# NFC_reva.net
KiCad netlist of a schematic drawn in EAGLE
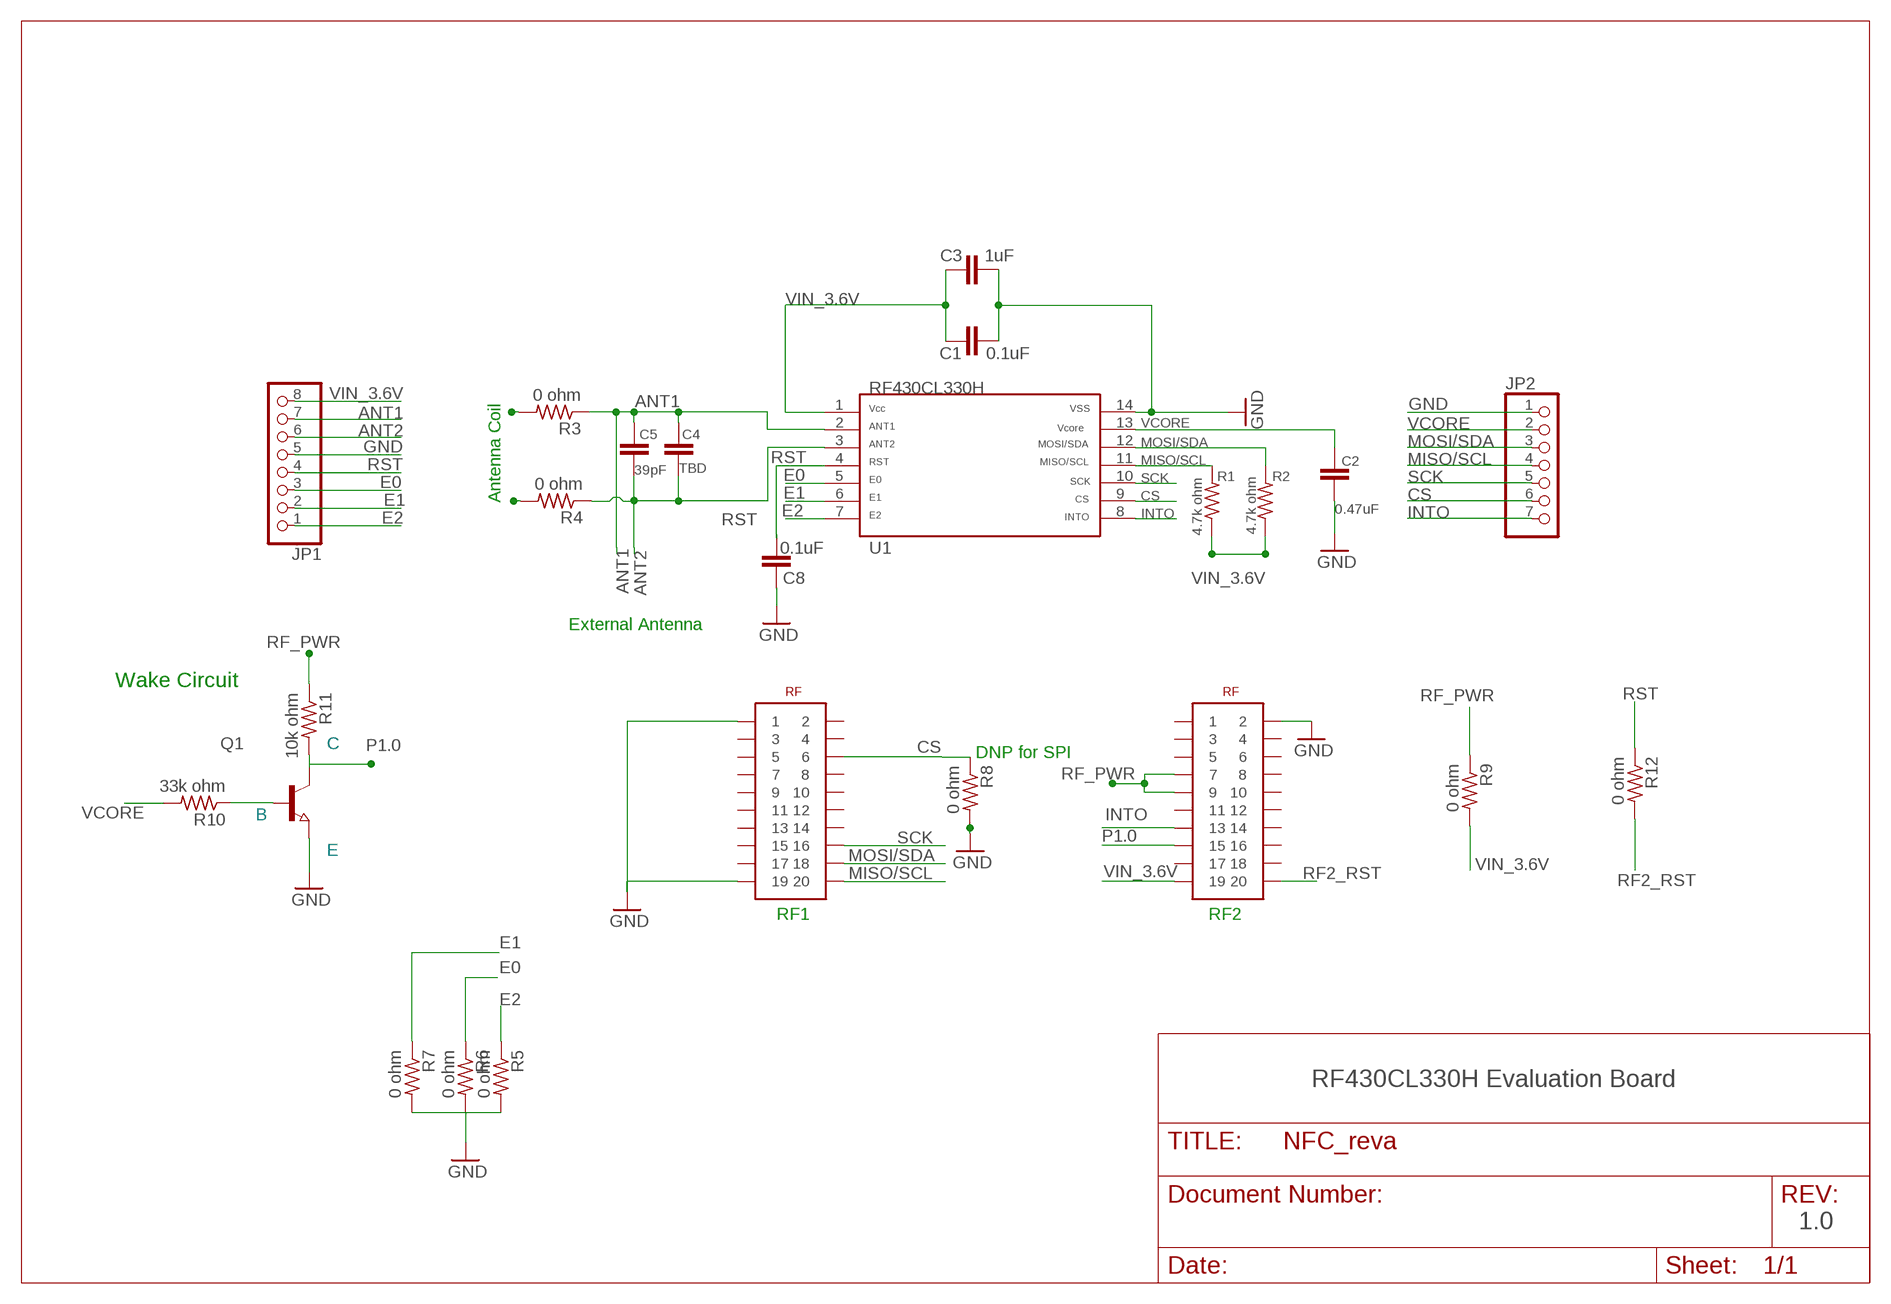
[diagram p0: schematic, sheet 1]

(export (version "E")
  (design (tool "Eeschema 10.0.6"))
  (components
    (comp (ref "C1")
      (value "0.1uF")
      (footprint "eagle-import:C0603")
      (libsource (lib "eagle-import") (part "C-EUC0603"))
    )
    (comp (ref "C2")
      (value "0.47uF")
      (footprint "eagle-import:C0603")
      (libsource (lib "eagle-import") (part "C-EUC0603"))
    )
    (comp (ref "C3")
      (value "1uF")
      (footprint "eagle-import:C0603")
      (libsource (lib "eagle-import") (part "C-EUC0603"))
    )
    (comp (ref "C4")
      (value "TBD")
      (footprint "eagle-import:C0603")
      (libsource (lib "eagle-import") (part "C-EUC0603"))
    )
    (comp (ref "C5")
      (value "39pF")
      (footprint "eagle-import:C0603")
      (libsource (lib "eagle-import") (part "C-EUC0603"))
    )
    (comp (ref "C8")
      (value "0.1uF")
      (footprint "eagle-import:C0603")
      (libsource (lib "eagle-import") (part "C-EUC0603"))
    )
    (comp (ref "JP1")
      (value "PINHD-1X8")
      (footprint "eagle-import:1X08")
      (libsource (lib "eagle-import") (part "PINHD-1X8"))
    )
    (comp (ref "JP2")
      (value "PINHD-1X7")
      (footprint "eagle-import:1X07")
      (libsource (lib "eagle-import") (part "PINHD-1X7"))
    )
    (comp (ref "Q1")
      (value "NPN-TRANSISTOR_SOT23")
      (footprint "eagle-import:SOT23")
      (libsource (lib "eagle-import") (part "NPN-TRANSISTOR_SOT23"))
    )
    (comp (ref "R1")
      (value "4.7k ohm")
      (footprint "eagle-import:R0402")
      (libsource (lib "eagle-import") (part "R-US_R0402"))
    )
    (comp (ref "R2")
      (value "4.7k ohm")
      (footprint "eagle-import:R0402")
      (libsource (lib "eagle-import") (part "R-US_R0402"))
    )
    (comp (ref "R3")
      (value "0 ohm")
      (footprint "eagle-import:R0402")
      (libsource (lib "eagle-import") (part "R-US_R0402"))
    )
    (comp (ref "R4")
      (value "0 ohm")
      (footprint "eagle-import:R0402")
      (libsource (lib "eagle-import") (part "R-US_R0402"))
    )
    (comp (ref "R5")
      (value "0 ohm")
      (footprint "eagle-import:R0402")
      (libsource (lib "eagle-import") (part "R-US_R0402"))
    )
    (comp (ref "R6")
      (value "0 ohm")
      (footprint "eagle-import:R0402")
      (libsource (lib "eagle-import") (part "R-US_R0402"))
    )
    (comp (ref "R7")
      (value "0 ohm")
      (footprint "eagle-import:R0402")
      (libsource (lib "eagle-import") (part "R-US_R0402"))
    )
    (comp (ref "R8")
      (value "0 ohm")
      (footprint "eagle-import:R0402")
      (libsource (lib "eagle-import") (part "R-US_R0402"))
    )
    (comp (ref "R9")
      (value "0 ohm")
      (footprint "eagle-import:R0402")
      (libsource (lib "eagle-import") (part "R-US_R0402"))
    )
    (comp (ref "R10")
      (value "33k ohm")
      (footprint "eagle-import:R0402")
      (libsource (lib "eagle-import") (part "R-US_R0402"))
    )
    (comp (ref "R11")
      (value "10k ohm")
      (footprint "eagle-import:R0402")
      (libsource (lib "eagle-import") (part "R-US_R0402"))
    )
    (comp (ref "R12")
      (value "0 ohm")
      (footprint "eagle-import:R0402")
      (libsource (lib "eagle-import") (part "R-US_R0402"))
    )
    (comp (ref "RF_HEADER")
      (value "EM_HEADER")
      (footprint "eagle-import:TFM-110-02-SM-D-A-K")
      (libsource (lib "eagle-import") (part "EM_HEADER"))
    )
    (comp (ref "U1")
      (value "RF430CL330H")
      (footprint "eagle-import:PW14")
      (libsource (lib "eagle-import") (part "RF430CL330H"))
    )
  )
  (nets
    (net (code "1") (name "/ANT1") (class "Default")
      (node (ref "C4") (pin "1") (pinfunction "1_1") (pintype "passive"))
      (node (ref "C5") (pin "1") (pinfunction "1_1") (pintype "passive"))
      (node (ref "JP1") (pin "7") (pinfunction "7_7") (pintype "passive"))
      (node (ref "R3") (pin "1") (pinfunction "1_1") (pintype "passive"))
      (node (ref "U1") (pin "2") (pinfunction "2_2") (pintype "bidirectional"))
    )
    (net (code "2") (name "/ANT2") (class "Default")
      (node (ref "C4") (pin "2") (pinfunction "2_2") (pintype "passive"))
      (node (ref "C5") (pin "2") (pinfunction "2_2") (pintype "passive"))
      (node (ref "JP1") (pin "6") (pinfunction "6_6") (pintype "passive"))
      (node (ref "R4") (pin "1") (pinfunction "1_1") (pintype "passive"))
      (node (ref "U1") (pin "3") (pinfunction "3_3") (pintype "bidirectional"))
    )
    (net (code "3") (name "/CS") (class "Default")
      (node (ref "JP2") (pin "6") (pinfunction "6_6") (pintype "passive"))
      (node (ref "R8") (pin "1") (pinfunction "1_1") (pintype "passive"))
      (node (ref "RF_HEADER") (pin "6") (pinfunction "6_6") (pintype "bidirectional"))
      (node (ref "U1") (pin "9") (pinfunction "9_9") (pintype "bidirectional"))
    )
    (net (code "4") (name "/E0") (class "Default")
      (node (ref "JP1") (pin "3") (pinfunction "3_3") (pintype "passive"))
      (node (ref "R6") (pin "1") (pinfunction "1_1") (pintype "passive"))
      (node (ref "U1") (pin "5") (pinfunction "5_5") (pintype "bidirectional"))
    )
    (net (code "5") (name "/E1") (class "Default")
      (node (ref "JP1") (pin "2") (pinfunction "2_2") (pintype "passive"))
      (node (ref "R7") (pin "1") (pinfunction "1_1") (pintype "passive"))
      (node (ref "U1") (pin "6") (pinfunction "6_6") (pintype "bidirectional"))
    )
    (net (code "6") (name "/E2") (class "Default")
      (node (ref "JP1") (pin "1") (pinfunction "1_1") (pintype "passive"))
      (node (ref "R5") (pin "1") (pinfunction "1_1") (pintype "passive"))
      (node (ref "U1") (pin "7") (pinfunction "7_7") (pintype "bidirectional"))
    )
    (net (code "7") (name "/INTO") (class "Default")
      (node (ref "JP2") (pin "7") (pinfunction "7_7") (pintype "passive"))
      (node (ref "RF_HEADER") (pin "33") (pinfunction "13_33") (pintype "bidirectional"))
      (node (ref "U1") (pin "8") (pinfunction "8_8") (pintype "bidirectional"))
    )
    (net (code "8") (name "/MISO{slash}SCL") (class "Default")
      (node (ref "JP2") (pin "4") (pinfunction "4_4") (pintype "passive"))
      (node (ref "R1") (pin "2") (pinfunction "2_2") (pintype "passive"))
      (node (ref "RF_HEADER") (pin "20") (pinfunction "20_20") (pintype "bidirectional"))
      (node (ref "U1") (pin "11") (pinfunction "11_11") (pintype "bidirectional"))
    )
    (net (code "9") (name "/MOSI{slash}SDA") (class "Default")
      (node (ref "JP2") (pin "3") (pinfunction "3_3") (pintype "passive"))
      (node (ref "R2") (pin "2") (pinfunction "2_2") (pintype "passive"))
      (node (ref "RF_HEADER") (pin "18") (pinfunction "18_18") (pintype "bidirectional"))
      (node (ref "U1") (pin "12") (pinfunction "12_12") (pintype "bidirectional"))
    )
    (net (code "10") (name "/P1.0") (class "Default")
      (node (ref "Q1") (pin "3") (pinfunction "C_3") (pintype "passive"))
      (node (ref "R11") (pin "2") (pinfunction "2_2") (pintype "passive"))
      (node (ref "RF_HEADER") (pin "35") (pinfunction "15_35") (pintype "bidirectional"))
    )
    (net (code "11") (name "/RF2_RST") (class "Default")
      (node (ref "R12") (pin "2") (pinfunction "2_2") (pintype "passive"))
      (node (ref "RF_HEADER") (pin "40") (pinfunction "20_40") (pintype "bidirectional"))
    )
    (net (code "12") (name "/RF_PWR") (class "Default")
      (node (ref "R11") (pin "1") (pinfunction "1_1") (pintype "passive"))
      (node (ref "R9") (pin "1") (pinfunction "1_1") (pintype "passive"))
      (node (ref "RF_HEADER") (pin "27") (pinfunction "7_27") (pintype "bidirectional"))
      (node (ref "RF_HEADER") (pin "29") (pinfunction "9_29") (pintype "bidirectional"))
    )
    (net (code "13") (name "/RST") (class "Default")
      (node (ref "C8") (pin "2") (pinfunction "2_2") (pintype "passive"))
      (node (ref "JP1") (pin "4") (pinfunction "4_4") (pintype "passive"))
      (node (ref "R12") (pin "1") (pinfunction "1_1") (pintype "passive"))
      (node (ref "U1") (pin "4") (pinfunction "4_4") (pintype "bidirectional"))
    )
    (net (code "14") (name "/SCK") (class "Default")
      (node (ref "JP2") (pin "5") (pinfunction "5_5") (pintype "passive"))
      (node (ref "RF_HEADER") (pin "16") (pinfunction "16_16") (pintype "bidirectional"))
      (node (ref "U1") (pin "10") (pinfunction "10_10") (pintype "bidirectional"))
    )
    (net (code "15") (name "/VCORE") (class "Default")
      (node (ref "C2") (pin "1") (pinfunction "1_1") (pintype "passive"))
      (node (ref "JP2") (pin "2") (pinfunction "2_2") (pintype "passive"))
      (node (ref "R10") (pin "2") (pinfunction "2_2") (pintype "passive"))
      (node (ref "U1") (pin "13") (pinfunction "13_13") (pintype "bidirectional"))
    )
    (net (code "16") (name "/VIN_3.6V") (class "Default")
      (node (ref "C1") (pin "1") (pinfunction "1_1") (pintype "passive"))
      (node (ref "C3") (pin "1") (pinfunction "1_1") (pintype "passive"))
      (node (ref "JP1") (pin "8") (pinfunction "8_8") (pintype "passive"))
      (node (ref "R1") (pin "1") (pinfunction "1_1") (pintype "passive"))
      (node (ref "R2") (pin "1") (pinfunction "1_1") (pintype "passive"))
      (node (ref "R9") (pin "2") (pinfunction "2_2") (pintype "passive"))
      (node (ref "RF_HEADER") (pin "39") (pinfunction "19_39") (pintype "bidirectional"))
      (node (ref "U1") (pin "1") (pinfunction "1_1") (pintype "bidirectional"))
    )
    (net (code "17") (name "GND") (class "Default")
      (node (ref "C1") (pin "2") (pinfunction "2_2") (pintype "passive"))
      (node (ref "C2") (pin "2") (pinfunction "2_2") (pintype "passive"))
      (node (ref "C3") (pin "2") (pinfunction "2_2") (pintype "passive"))
      (node (ref "C8") (pin "1") (pinfunction "1_1") (pintype "passive"))
      (node (ref "JP1") (pin "5") (pinfunction "5_5") (pintype "passive"))
      (node (ref "JP2") (pin "1") (pinfunction "1_1") (pintype "passive"))
      (node (ref "Q1") (pin "2") (pinfunction "E_2") (pintype "passive"))
      (node (ref "R5") (pin "2") (pinfunction "2_2") (pintype "passive"))
      (node (ref "R6") (pin "2") (pinfunction "2_2") (pintype "passive"))
      (node (ref "R7") (pin "2") (pinfunction "2_2") (pintype "passive"))
      (node (ref "R8") (pin "2") (pinfunction "2_2") (pintype "passive"))
      (node (ref "RF_HEADER") (pin "1") (pinfunction "1_1") (pintype "bidirectional"))
      (node (ref "RF_HEADER") (pin "19") (pinfunction "19_19") (pintype "bidirectional"))
      (node (ref "RF_HEADER") (pin "22") (pinfunction "2_22") (pintype "bidirectional"))
      (node (ref "U1") (pin "14") (pinfunction "14_14") (pintype "bidirectional"))
    )
    (net (code "18") (name "Net-(Q1-B)") (class "Default")
      (node (ref "Q1") (pin "1") (pinfunction "B_1") (pintype "passive"))
      (node (ref "R10") (pin "1") (pinfunction "1_1") (pintype "passive"))
    )
    (net (code "19") (name "unconnected-(R3-Pad2)") (class "Default")
      (node (ref "R3") (pin "2") (pinfunction "2_2") (pintype "passive"))
    )
    (net (code "20") (name "unconnected-(R4-Pad2)") (class "Default")
      (node (ref "R4") (pin "2") (pinfunction "2_2") (pintype "passive"))
    )
    (net (code "21") (name "unconnected-(RF_HEADER-Pad2)") (class "Default")
      (node (ref "RF_HEADER") (pin "2") (pinfunction "2_2") (pintype "bidirectional"))
    )
    (net (code "22") (name "unconnected-(RF_HEADER-Pad3)") (class "Default")
      (node (ref "RF_HEADER") (pin "3") (pinfunction "3_3") (pintype "bidirectional"))
    )
    (net (code "23") (name "unconnected-(RF_HEADER-Pad4)") (class "Default")
      (node (ref "RF_HEADER") (pin "4") (pinfunction "4_4") (pintype "bidirectional"))
    )
    (net (code "24") (name "unconnected-(RF_HEADER-Pad5)") (class "Default")
      (node (ref "RF_HEADER") (pin "5") (pinfunction "5_5") (pintype "bidirectional"))
    )
    (net (code "25") (name "unconnected-(RF_HEADER-Pad7)") (class "Default")
      (node (ref "RF_HEADER") (pin "7") (pinfunction "7_7") (pintype "bidirectional"))
    )
    (net (code "26") (name "unconnected-(RF_HEADER-Pad8)") (class "Default")
      (node (ref "RF_HEADER") (pin "8") (pinfunction "8_8") (pintype "bidirectional"))
    )
    (net (code "27") (name "unconnected-(RF_HEADER-Pad9)") (class "Default")
      (node (ref "RF_HEADER") (pin "9") (pinfunction "9_9") (pintype "bidirectional"))
    )
    (net (code "28") (name "unconnected-(RF_HEADER-Pad10)") (class "Default")
      (node (ref "RF_HEADER") (pin "10") (pinfunction "10_10") (pintype "bidirectional"))
    )
    (net (code "29") (name "unconnected-(RF_HEADER-Pad11)") (class "Default")
      (node (ref "RF_HEADER") (pin "11") (pinfunction "11_11") (pintype "bidirectional"))
    )
    (net (code "30") (name "unconnected-(RF_HEADER-Pad12)") (class "Default")
      (node (ref "RF_HEADER") (pin "12") (pinfunction "12_12") (pintype "bidirectional"))
    )
    (net (code "31") (name "unconnected-(RF_HEADER-Pad13)") (class "Default")
      (node (ref "RF_HEADER") (pin "13") (pinfunction "13_13") (pintype "bidirectional"))
    )
    (net (code "32") (name "unconnected-(RF_HEADER-Pad14)") (class "Default")
      (node (ref "RF_HEADER") (pin "14") (pinfunction "14_14") (pintype "bidirectional"))
    )
    (net (code "33") (name "unconnected-(RF_HEADER-Pad15)") (class "Default")
      (node (ref "RF_HEADER") (pin "15") (pinfunction "15_15") (pintype "bidirectional"))
    )
    (net (code "34") (name "unconnected-(RF_HEADER-Pad17)") (class "Default")
      (node (ref "RF_HEADER") (pin "17") (pinfunction "17_17") (pintype "bidirectional"))
    )
    (net (code "35") (name "unconnected-(RF_HEADERB-1-Pad21)") (class "Default")
      (node (ref "RF_HEADER") (pin "21") (pinfunction "1_21") (pintype "bidirectional"))
    )
    (net (code "36") (name "unconnected-(RF_HEADERB-3-Pad23)") (class "Default")
      (node (ref "RF_HEADER") (pin "23") (pinfunction "3_23") (pintype "bidirectional"))
    )
    (net (code "37") (name "unconnected-(RF_HEADERB-4-Pad24)") (class "Default")
      (node (ref "RF_HEADER") (pin "24") (pinfunction "4_24") (pintype "bidirectional"))
    )
    (net (code "38") (name "unconnected-(RF_HEADERB-5-Pad25)") (class "Default")
      (node (ref "RF_HEADER") (pin "25") (pinfunction "5_25") (pintype "bidirectional"))
    )
    (net (code "39") (name "unconnected-(RF_HEADERB-6-Pad26)") (class "Default")
      (node (ref "RF_HEADER") (pin "26") (pinfunction "6_26") (pintype "bidirectional"))
    )
    (net (code "40") (name "unconnected-(RF_HEADERB-8-Pad28)") (class "Default")
      (node (ref "RF_HEADER") (pin "28") (pinfunction "8_28") (pintype "bidirectional"))
    )
    (net (code "41") (name "unconnected-(RF_HEADERB-10-Pad30)") (class "Default")
      (node (ref "RF_HEADER") (pin "30") (pinfunction "10_30") (pintype "bidirectional"))
    )
    (net (code "42") (name "unconnected-(RF_HEADERB-11-Pad31)") (class "Default")
      (node (ref "RF_HEADER") (pin "31") (pinfunction "11_31") (pintype "bidirectional"))
    )
    (net (code "43") (name "unconnected-(RF_HEADERB-12-Pad32)") (class "Default")
      (node (ref "RF_HEADER") (pin "32") (pinfunction "12_32") (pintype "bidirectional"))
    )
    (net (code "44") (name "unconnected-(RF_HEADERB-14-Pad34)") (class "Default")
      (node (ref "RF_HEADER") (pin "34") (pinfunction "14_34") (pintype "bidirectional"))
    )
    (net (code "45") (name "unconnected-(RF_HEADERB-16-Pad36)") (class "Default")
      (node (ref "RF_HEADER") (pin "36") (pinfunction "16_36") (pintype "bidirectional"))
    )
    (net (code "46") (name "unconnected-(RF_HEADERB-17-Pad37)") (class "Default")
      (node (ref "RF_HEADER") (pin "37") (pinfunction "17_37") (pintype "bidirectional"))
    )
    (net (code "47") (name "unconnected-(RF_HEADERB-18-Pad38)") (class "Default")
      (node (ref "RF_HEADER") (pin "38") (pinfunction "18_38") (pintype "bidirectional"))
    )
  )
)
